# proiectPM.net
KiCad netlist of a schematic drawn in EAGLE
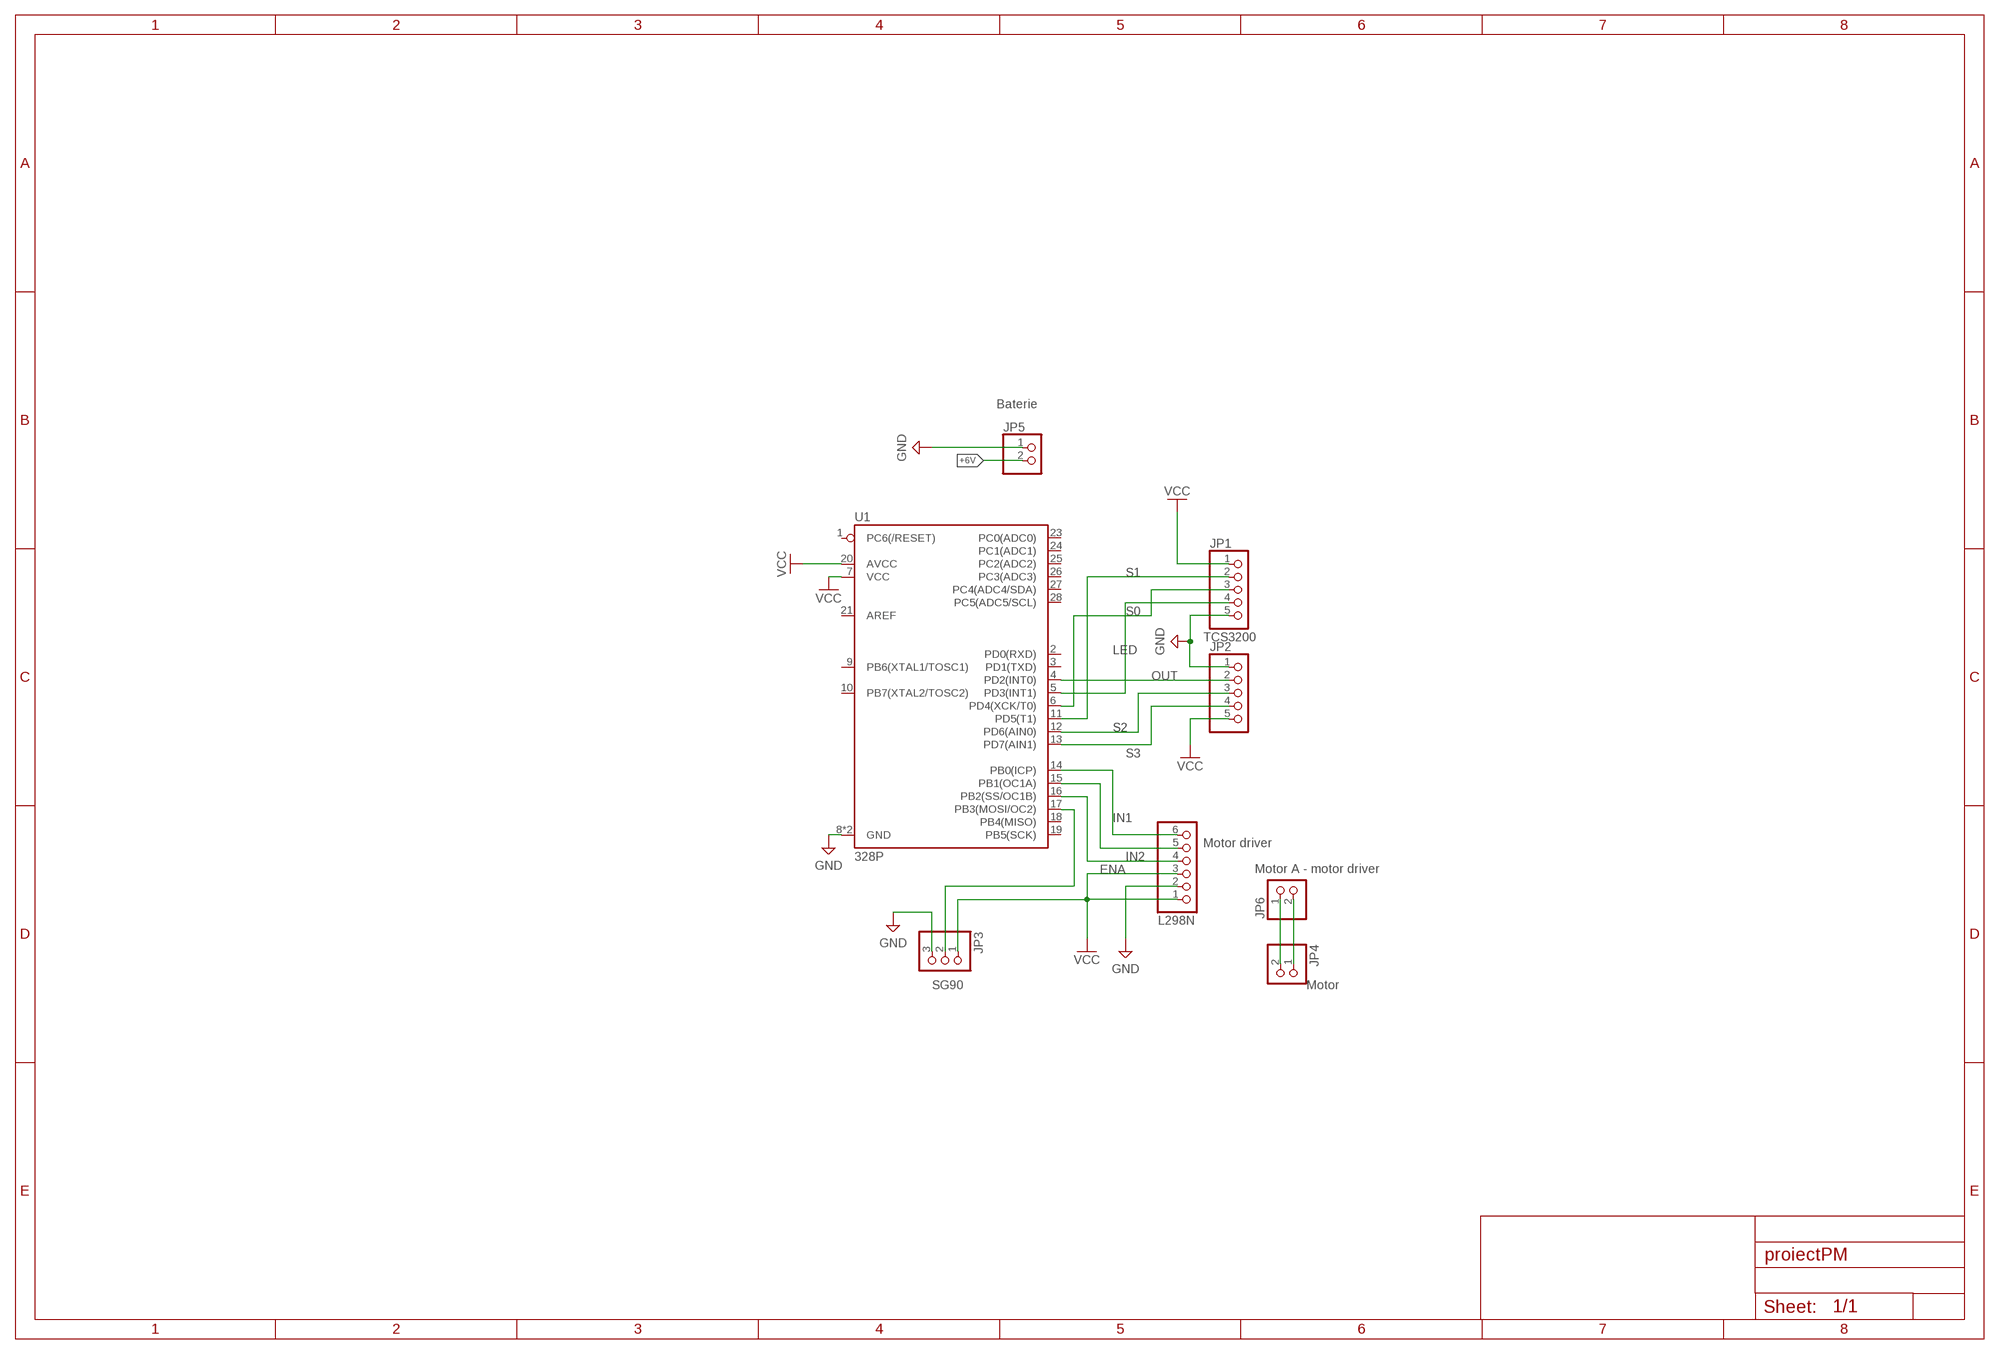
[diagram p0: schematic, sheet 1]

(export (version "E")
  (design (tool "Eeschema 10.0.6"))
  (components
    (comp (ref "JP1")
      (value "PINHD-1X5")
      (footprint "eagle-import:1X05")
      (libsource (lib "eagle-import") (part "PINHD-1X5"))
    )
    (comp (ref "JP2")
      (value "PINHD-1X5")
      (footprint "eagle-import:1X05")
      (libsource (lib "eagle-import") (part "PINHD-1X5"))
    )
    (comp (ref "JP3")
      (value "PINHD-1X3")
      (footprint "eagle-import:1X03")
      (libsource (lib "eagle-import") (part "PINHD-1X3"))
    )
    (comp (ref "JP4")
      (value "PINHD-1X2")
      (footprint "eagle-import:1X02")
      (libsource (lib "eagle-import") (part "PINHD-1X2"))
    )
    (comp (ref "JP5")
      (value "PINHD-1X2")
      (footprint "eagle-import:1X02")
      (libsource (lib "eagle-import") (part "PINHD-1X2"))
    )
    (comp (ref "JP6")
      (value "PINHD-1X2")
      (footprint "eagle-import:1X02")
      (libsource (lib "eagle-import") (part "PINHD-1X2"))
    )
    (comp (ref "L298N")
      (value "PINHD-1X6")
      (footprint "eagle-import:1X06")
      (libsource (lib "eagle-import") (part "PINHD-1X6"))
    )
    (comp (ref "U1")
      (value "328P")
      (footprint "eagle-import:DIP28")
      (libsource (lib "eagle-import") (part "ATMEGA328P_PDIP"))
    )
  )
  (nets
    (net (code "1") (name "+6V") (class "Default")
      (node (ref "JP5") (pin "2") (pinfunction "2_2") (pintype "passive"))
    )
    (net (code "2") (name "/ENA") (class "Default")
      (node (ref "L298N") (pin "4") (pinfunction "4_4") (pintype "passive"))
      (node (ref "U1") (pin "16") (pinfunction "PB2(SS/OC1B)_16") (pintype "bidirectional"))
    )
    (net (code "3") (name "/IN1") (class "Default")
      (node (ref "L298N") (pin "6") (pinfunction "6_6") (pintype "passive"))
      (node (ref "U1") (pin "14") (pinfunction "PB0(ICP)_14") (pintype "bidirectional"))
    )
    (net (code "4") (name "/IN2") (class "Default")
      (node (ref "L298N") (pin "5") (pinfunction "5_5") (pintype "passive"))
      (node (ref "U1") (pin "15") (pinfunction "PB1(OC1A)_15") (pintype "bidirectional"))
    )
    (net (code "5") (name "/LED") (class "Default")
      (node (ref "JP1") (pin "4") (pinfunction "4_4") (pintype "passive"))
      (node (ref "U1") (pin "5") (pinfunction "PD3(INT1)_5") (pintype "bidirectional"))
    )
    (net (code "6") (name "/OUT") (class "Default")
      (node (ref "JP2") (pin "2") (pinfunction "2_2") (pintype "passive"))
      (node (ref "U1") (pin "4") (pinfunction "PD2(INT0)_4") (pintype "bidirectional"))
    )
    (net (code "7") (name "/S0") (class "Default")
      (node (ref "JP1") (pin "3") (pinfunction "3_3") (pintype "passive"))
      (node (ref "U1") (pin "6") (pinfunction "PD4(XCK/T0)_6") (pintype "bidirectional"))
    )
    (net (code "8") (name "/S1") (class "Default")
      (node (ref "JP1") (pin "2") (pinfunction "2_2") (pintype "passive"))
      (node (ref "U1") (pin "11") (pinfunction "PD5(T1)_11") (pintype "bidirectional"))
    )
    (net (code "9") (name "/S2") (class "Default")
      (node (ref "JP2") (pin "3") (pinfunction "3_3") (pintype "passive"))
      (node (ref "U1") (pin "12") (pinfunction "PD6(AIN0)_12") (pintype "bidirectional"))
    )
    (net (code "10") (name "/S3") (class "Default")
      (node (ref "JP2") (pin "4") (pinfunction "4_4") (pintype "passive"))
      (node (ref "U1") (pin "13") (pinfunction "PD7(AIN1)_13") (pintype "bidirectional"))
    )
    (net (code "11") (name "GND") (class "Default")
      (node (ref "JP1") (pin "5") (pinfunction "5_5") (pintype "passive"))
      (node (ref "JP2") (pin "1") (pinfunction "1_1") (pintype "passive"))
      (node (ref "JP3") (pin "3") (pinfunction "3_3") (pintype "passive"))
      (node (ref "JP5") (pin "1") (pinfunction "1_1") (pintype "passive"))
      (node (ref "L298N") (pin "2") (pinfunction "2_2") (pintype "passive"))
      (node (ref "U1") (pin "22") (pinfunction "GND_22") (pintype "bidirectional"))
      (node (ref "U1") (pin "8") (pinfunction "GND_8") (pintype "bidirectional"))
    )
    (net (code "12") (name "Net-(JP4-Pad1)") (class "Default")
      (node (ref "JP4") (pin "1") (pinfunction "1_1") (pintype "passive"))
      (node (ref "JP6") (pin "2") (pinfunction "2_2") (pintype "passive"))
    )
    (net (code "13") (name "Net-(JP4-Pad2)") (class "Default")
      (node (ref "JP4") (pin "2") (pinfunction "2_2") (pintype "passive"))
      (node (ref "JP6") (pin "1") (pinfunction "1_1") (pintype "passive"))
    )
    (net (code "14") (name "Net-(U1-PB3(MOSI{slash}OC2))") (class "Default")
      (node (ref "JP3") (pin "2") (pinfunction "2_2") (pintype "passive"))
      (node (ref "U1") (pin "17") (pinfunction "PB3(MOSI/OC2)_17") (pintype "bidirectional"))
    )
    (net (code "15") (name "VCC") (class "Default")
      (node (ref "JP1") (pin "1") (pinfunction "1_1") (pintype "passive"))
      (node (ref "JP2") (pin "5") (pinfunction "5_5") (pintype "passive"))
      (node (ref "JP3") (pin "1") (pinfunction "1_1") (pintype "passive"))
      (node (ref "L298N") (pin "1") (pinfunction "1_1") (pintype "passive"))
      (node (ref "L298N") (pin "3") (pinfunction "3_3") (pintype "passive"))
      (node (ref "U1") (pin "20") (pinfunction "AVCC_20") (pintype "bidirectional"))
      (node (ref "U1") (pin "7") (pinfunction "VCC_7") (pintype "bidirectional"))
    )
    (net (code "16") (name "unconnected-(U1-AREF-Pad21)") (class "Default")
      (node (ref "U1") (pin "21") (pinfunction "AREF_21") (pintype "bidirectional"))
    )
    (net (code "17") (name "unconnected-(U1-PB4(MISO)-Pad18)") (class "Default")
      (node (ref "U1") (pin "18") (pinfunction "PB4(MISO)_18") (pintype "bidirectional"))
    )
    (net (code "18") (name "unconnected-(U1-PB5(SCK)-Pad19)") (class "Default")
      (node (ref "U1") (pin "19") (pinfunction "PB5(SCK)_19") (pintype "bidirectional"))
    )
    (net (code "19") (name "unconnected-(U1-PB6(XTAL1{slash}TOSC1)-Pad9)") (class "Default")
      (node (ref "U1") (pin "9") (pinfunction "PB6(XTAL1/TOSC1)_9") (pintype "bidirectional"))
    )
    (net (code "20") (name "unconnected-(U1-PB7(XTAL2{slash}TOSC2)-Pad10)") (class "Default")
      (node (ref "U1") (pin "10") (pinfunction "PB7(XTAL2/TOSC2)_10") (pintype "bidirectional"))
    )
    (net (code "21") (name "unconnected-(U1-PC0(ADC0)-Pad23)") (class "Default")
      (node (ref "U1") (pin "23") (pinfunction "PC0(ADC0)_23") (pintype "bidirectional"))
    )
    (net (code "22") (name "unconnected-(U1-PC1(ADC1)-Pad24)") (class "Default")
      (node (ref "U1") (pin "24") (pinfunction "PC1(ADC1)_24") (pintype "bidirectional"))
    )
    (net (code "23") (name "unconnected-(U1-PC2(ADC2)-Pad25)") (class "Default")
      (node (ref "U1") (pin "25") (pinfunction "PC2(ADC2)_25") (pintype "bidirectional"))
    )
    (net (code "24") (name "unconnected-(U1-PC3(ADC3)-Pad26)") (class "Default")
      (node (ref "U1") (pin "26") (pinfunction "PC3(ADC3)_26") (pintype "bidirectional"))
    )
    (net (code "25") (name "unconnected-(U1-PC4(ADC4{slash}SDA)-Pad27)") (class "Default")
      (node (ref "U1") (pin "27") (pinfunction "PC4(ADC4/SDA)_27") (pintype "bidirectional"))
    )
    (net (code "26") (name "unconnected-(U1-PC5(ADC5{slash}SCL)-Pad28)") (class "Default")
      (node (ref "U1") (pin "28") (pinfunction "PC5(ADC5/SCL)_28") (pintype "bidirectional"))
    )
    (net (code "27") (name "unconnected-(U1-PC6({slash}RESET)-Pad1)") (class "Default")
      (node (ref "U1") (pin "1") (pinfunction "PC6(/RESET)_1") (pintype "bidirectional"))
    )
    (net (code "28") (name "unconnected-(U1-PD0(RXD)-Pad2)") (class "Default")
      (node (ref "U1") (pin "2") (pinfunction "PD0(RXD)_2") (pintype "bidirectional"))
    )
    (net (code "29") (name "unconnected-(U1-PD1(TXD)-Pad3)") (class "Default")
      (node (ref "U1") (pin "3") (pinfunction "PD1(TXD)_3") (pintype "bidirectional"))
    )
  )
)
